# 4_Com_E_Sem_i2c.net
KiCad netlist of a schematic drawn in EAGLE
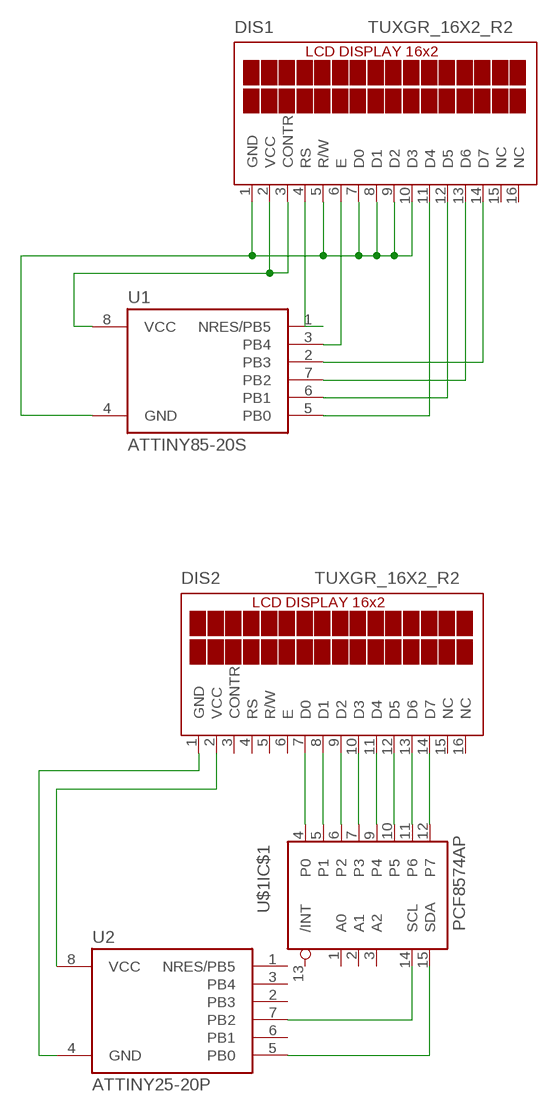
[diagram p0: schematic, sheet 1]

(export (version "E")
  (design (tool "Eeschema 10.0.6"))
  (components
    (comp (ref "DIS1")
      (value "TUXGR_16X2_R2")
      (footprint "eagle-import:TUXGR_16X2_R2")
      (libsource (lib "eagle-import") (part "TUXGR_16X2_R2"))
    )
    (comp (ref "DIS2")
      (value "TUXGR_16X2_R2")
      (footprint "eagle-import:TUXGR_16X2_R2")
      (libsource (lib "eagle-import") (part "TUXGR_16X2_R2"))
    )
    (comp (ref "U$1")
      (value "PCF8574AP")
      (footprint "eagle-import:DIL16")
      (libsource (lib "eagle-import") (part "PCF8574AP"))
    )
    (comp (ref "U1")
      (value "ATTINY85-20S")
      (footprint "eagle-import:SOIC8_EIAJ_208MIL")
      (libsource (lib "eagle-import") (part "ATTINY85S-20"))
    )
    (comp (ref "U2")
      (value "ATTINY25-20P")
      (footprint "eagle-import:PDIP08_300MIL")
      (libsource (lib "eagle-import") (part "ATTINY25P-20"))
    )
  )
  (nets
    (net (code "1") (name "Net-(DIS1-CONTR)") (class "Default")
      (node (ref "DIS1") (pin "2") (pinfunction "VCC_2") (pintype "power_in"))
      (node (ref "DIS1") (pin "3") (pinfunction "CONTR_3") (pintype "input"))
      (node (ref "U1") (pin "8") (pinfunction "VCC_8") (pintype "power_in"))
    )
    (net (code "2") (name "Net-(DIS1-D0)") (class "Default")
      (node (ref "DIS1") (pin "1") (pinfunction "GND_1") (pintype "power_in"))
      (node (ref "DIS1") (pin "10") (pinfunction "D3_10") (pintype "input"))
      (node (ref "DIS1") (pin "5") (pinfunction "R/W_5") (pintype "input"))
      (node (ref "DIS1") (pin "7") (pinfunction "D0_7") (pintype "input"))
      (node (ref "DIS1") (pin "8") (pinfunction "D1_8") (pintype "input"))
      (node (ref "DIS1") (pin "9") (pinfunction "D2_9") (pintype "input"))
      (node (ref "U1") (pin "4") (pinfunction "GND_4") (pintype "power_in"))
    )
    (net (code "3") (name "Net-(DIS1-D4)") (class "Default")
      (node (ref "DIS1") (pin "11") (pinfunction "D4_11") (pintype "input"))
      (node (ref "U1") (pin "5") (pinfunction "PB0_5") (pintype "bidirectional"))
    )
    (net (code "4") (name "Net-(DIS1-D5)") (class "Default")
      (node (ref "DIS1") (pin "12") (pinfunction "D5_12") (pintype "input"))
      (node (ref "U1") (pin "6") (pinfunction "PB1_6") (pintype "bidirectional"))
    )
    (net (code "5") (name "Net-(DIS1-D6)") (class "Default")
      (node (ref "DIS1") (pin "13") (pinfunction "D6_13") (pintype "input"))
      (node (ref "U1") (pin "7") (pinfunction "PB2_7") (pintype "bidirectional"))
    )
    (net (code "6") (name "Net-(DIS1-D7)") (class "Default")
      (node (ref "DIS1") (pin "14") (pinfunction "D7_14") (pintype "input"))
      (node (ref "U1") (pin "2") (pinfunction "PB3_2") (pintype "bidirectional"))
    )
    (net (code "7") (name "Net-(DIS1-E)") (class "Default")
      (node (ref "DIS1") (pin "6") (pinfunction "E_6") (pintype "input"))
      (node (ref "U1") (pin "3") (pinfunction "PB4_3") (pintype "bidirectional"))
    )
    (net (code "8") (name "Net-(DIS1-RS)") (class "Default")
      (node (ref "DIS1") (pin "4") (pinfunction "RS_4") (pintype "input"))
      (node (ref "U1") (pin "1") (pinfunction "NRES/PB5_1") (pintype "bidirectional"))
    )
    (net (code "9") (name "Net-(DIS2-D0)") (class "Default")
      (node (ref "DIS2") (pin "7") (pinfunction "D0_7") (pintype "input"))
      (node (ref "U$1") (pin "4") (pinfunction "P0_4") (pintype "bidirectional"))
    )
    (net (code "10") (name "Net-(DIS2-D1)") (class "Default")
      (node (ref "DIS2") (pin "8") (pinfunction "D1_8") (pintype "input"))
      (node (ref "U$1") (pin "5") (pinfunction "P1_5") (pintype "bidirectional"))
    )
    (net (code "11") (name "Net-(DIS2-D2)") (class "Default")
      (node (ref "DIS2") (pin "9") (pinfunction "D2_9") (pintype "input"))
      (node (ref "U$1") (pin "6") (pinfunction "P2_6") (pintype "bidirectional"))
    )
    (net (code "12") (name "Net-(DIS2-D3)") (class "Default")
      (node (ref "DIS2") (pin "10") (pinfunction "D3_10") (pintype "input"))
      (node (ref "U$1") (pin "7") (pinfunction "P3_7") (pintype "bidirectional"))
    )
    (net (code "13") (name "Net-(DIS2-D4)") (class "Default")
      (node (ref "DIS2") (pin "11") (pinfunction "D4_11") (pintype "input"))
      (node (ref "U$1") (pin "9") (pinfunction "P4_9") (pintype "bidirectional"))
    )
    (net (code "14") (name "Net-(DIS2-D5)") (class "Default")
      (node (ref "DIS2") (pin "12") (pinfunction "D5_12") (pintype "input"))
      (node (ref "U$1") (pin "10") (pinfunction "P5_10") (pintype "bidirectional"))
    )
    (net (code "15") (name "Net-(DIS2-D6)") (class "Default")
      (node (ref "DIS2") (pin "13") (pinfunction "D6_13") (pintype "input"))
      (node (ref "U$1") (pin "11") (pinfunction "P6_11") (pintype "bidirectional"))
    )
    (net (code "16") (name "Net-(DIS2-D7)") (class "Default")
      (node (ref "DIS2") (pin "14") (pinfunction "D7_14") (pintype "input"))
      (node (ref "U$1") (pin "12") (pinfunction "P7_12") (pintype "bidirectional"))
    )
    (net (code "17") (name "Net-(DIS2-GND)") (class "Default")
      (node (ref "DIS2") (pin "1") (pinfunction "GND_1") (pintype "power_in"))
      (node (ref "U2") (pin "4") (pinfunction "GND_4") (pintype "power_in"))
    )
    (net (code "18") (name "Net-(DIS2-VCC)") (class "Default")
      (node (ref "DIS2") (pin "2") (pinfunction "VCC_2") (pintype "power_in"))
      (node (ref "U2") (pin "8") (pinfunction "VCC_8") (pintype "power_in"))
    )
    (net (code "19") (name "Net-(U$1A-SCL)") (class "Default")
      (node (ref "U$1") (pin "14") (pinfunction "SCL_14") (pintype "input"))
      (node (ref "U2") (pin "7") (pinfunction "PB2_7") (pintype "bidirectional"))
    )
    (net (code "20") (name "Net-(U$1A-SDA)") (class "Default")
      (node (ref "U$1") (pin "15") (pinfunction "SDA_15") (pintype "bidirectional"))
      (node (ref "U2") (pin "5") (pinfunction "PB0_5") (pintype "bidirectional"))
    )
    (net (code "21") (name "unconnected-(DIS1-NC-Pad15)") (class "Default")
      (node (ref "DIS1") (pin "15") (pinfunction "NC_15") (pintype "no_connect"))
    )
    (net (code "22") (name "unconnected-(DIS1-NC-Pad16)") (class "Default")
      (node (ref "DIS1") (pin "16") (pinfunction "NC_16") (pintype "no_connect"))
    )
    (net (code "23") (name "unconnected-(DIS2-CONTR-Pad3)") (class "Default")
      (node (ref "DIS2") (pin "3") (pinfunction "CONTR_3") (pintype "input"))
    )
    (net (code "24") (name "unconnected-(DIS2-E-Pad6)") (class "Default")
      (node (ref "DIS2") (pin "6") (pinfunction "E_6") (pintype "input"))
    )
    (net (code "25") (name "unconnected-(DIS2-NC-Pad15)") (class "Default")
      (node (ref "DIS2") (pin "15") (pinfunction "NC_15") (pintype "no_connect"))
    )
    (net (code "26") (name "unconnected-(DIS2-NC-Pad16)") (class "Default")
      (node (ref "DIS2") (pin "16") (pinfunction "NC_16") (pintype "no_connect"))
    )
    (net (code "27") (name "unconnected-(DIS2-RS-Pad4)") (class "Default")
      (node (ref "DIS2") (pin "4") (pinfunction "RS_4") (pintype "input"))
    )
    (net (code "28") (name "unconnected-(DIS2-R{slash}W-Pad5)") (class "Default")
      (node (ref "DIS2") (pin "5") (pinfunction "R/W_5") (pintype "input"))
    )
    (net (code "29") (name "unconnected-(U$1A-A0-Pad1)") (class "Default")
      (node (ref "U$1") (pin "1") (pinfunction "A0_1") (pintype "input"))
    )
    (net (code "30") (name "unconnected-(U$1A-A1-Pad2)") (class "Default")
      (node (ref "U$1") (pin "2") (pinfunction "A1_2") (pintype "input"))
    )
    (net (code "31") (name "unconnected-(U$1A-A2-Pad3)") (class "Default")
      (node (ref "U$1") (pin "3") (pinfunction "A2_3") (pintype "input"))
    )
    (net (code "32") (name "unconnected-(U$1A-{slash}INT-Pad13)") (class "Default")
      (node (ref "U$1") (pin "13") (pinfunction "/INT_13") (pintype "output"))
    )
    (net (code "33") (name "unconnected-(U2-NRES{slash}PB5-Pad1)") (class "Default")
      (node (ref "U2") (pin "1") (pinfunction "NRES/PB5_1") (pintype "bidirectional"))
    )
    (net (code "34") (name "unconnected-(U2-PB1-Pad6)") (class "Default")
      (node (ref "U2") (pin "6") (pinfunction "PB1_6") (pintype "bidirectional"))
    )
    (net (code "35") (name "unconnected-(U2-PB3-Pad2)") (class "Default")
      (node (ref "U2") (pin "2") (pinfunction "PB3_2") (pintype "bidirectional"))
    )
    (net (code "36") (name "unconnected-(U2-PB4-Pad3)") (class "Default")
      (node (ref "U2") (pin "3") (pinfunction "PB4_3") (pintype "bidirectional"))
    )
  )
)
